# Solarduino_V0_4.net
KiCad netlist of a schematic drawn in EAGLE
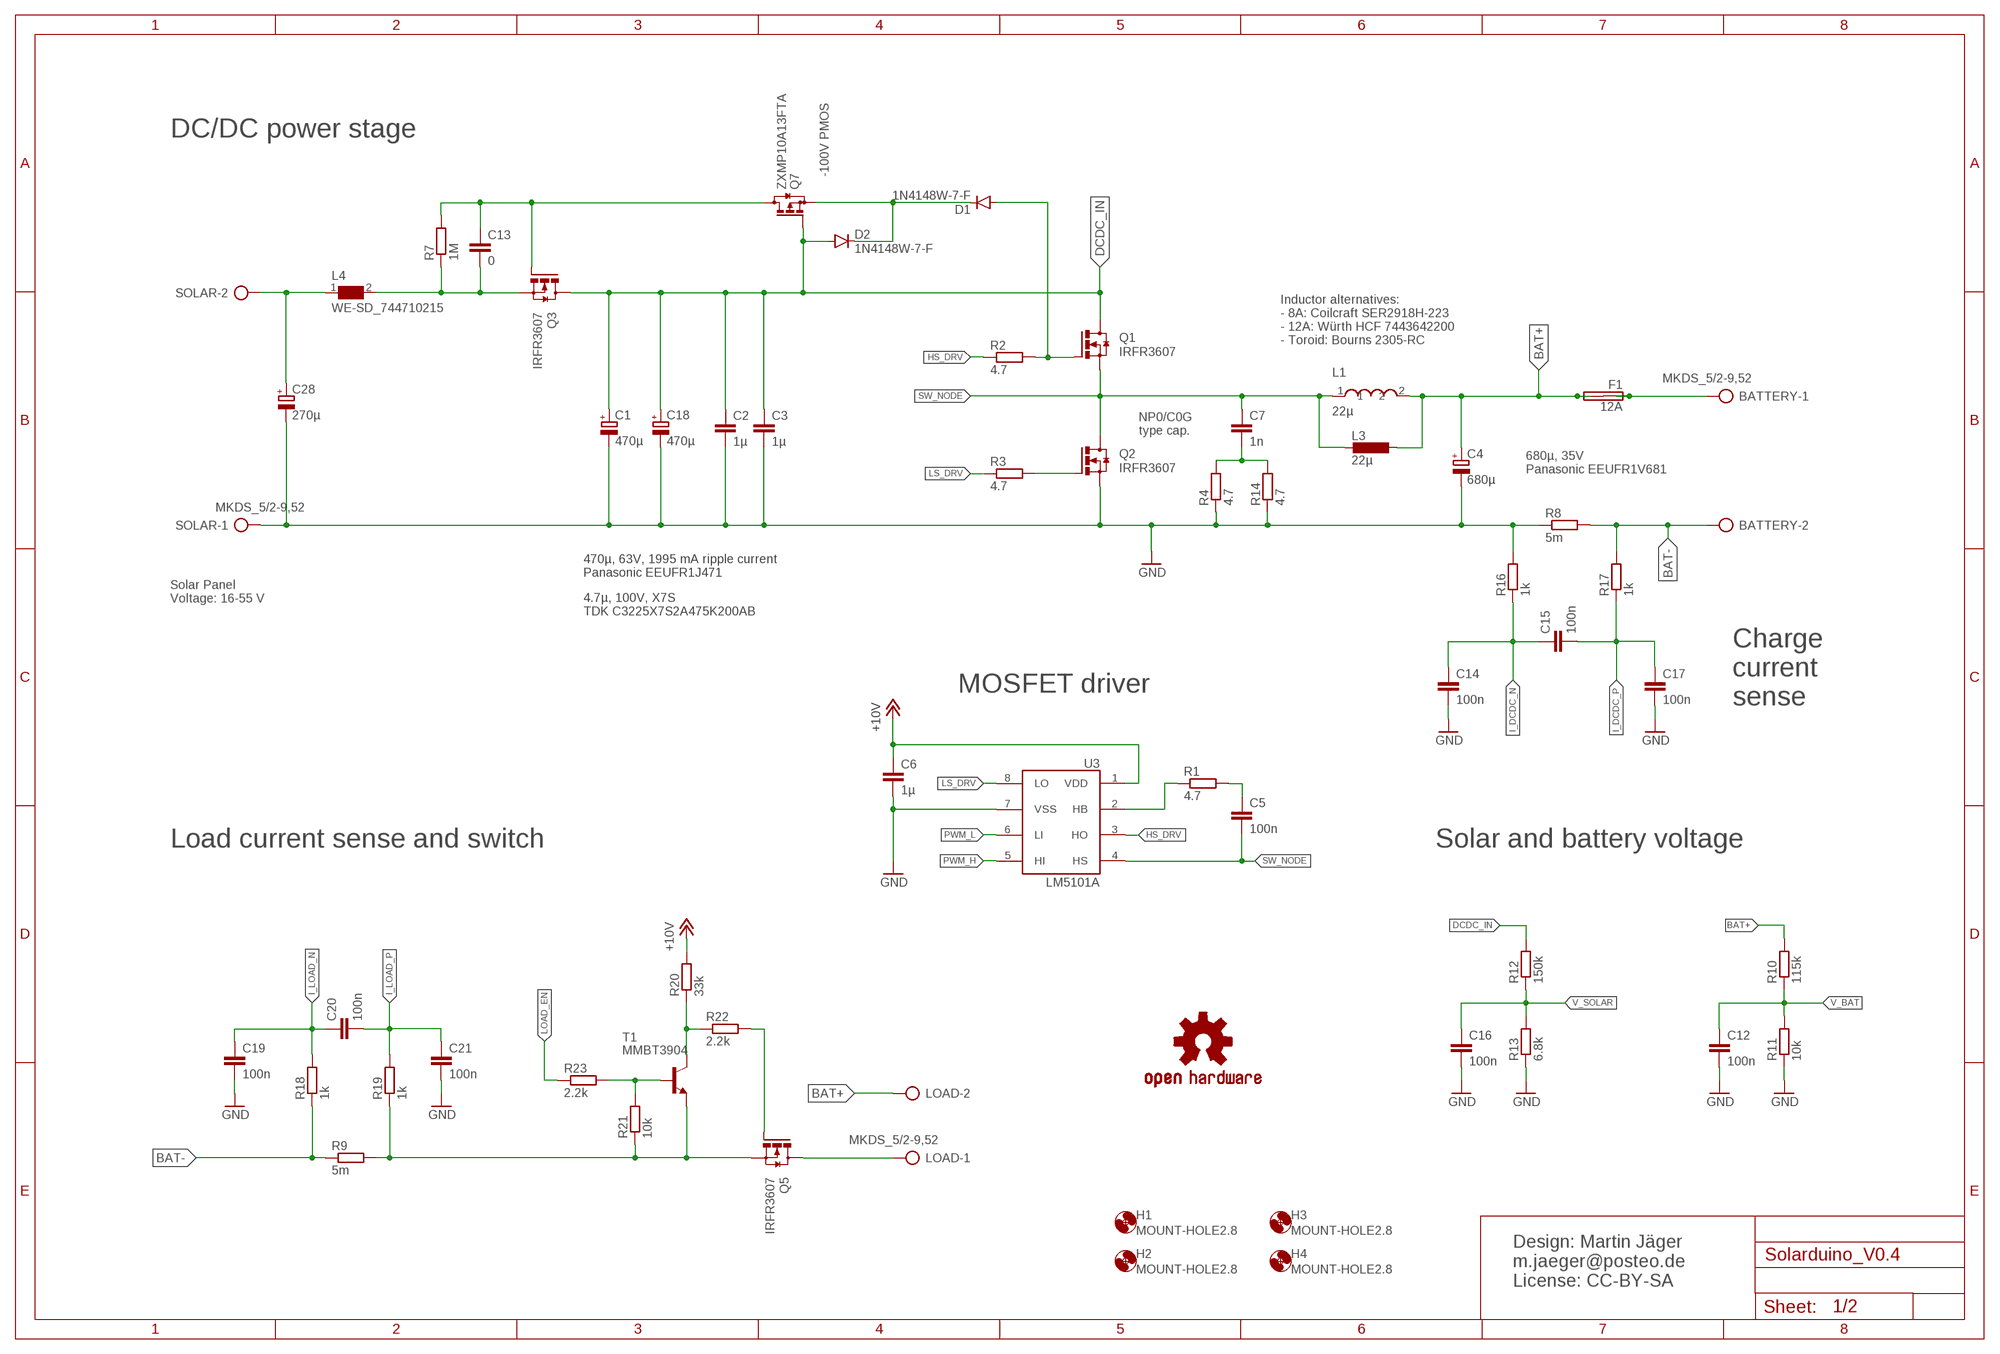
[diagram p0: schematic, sheet 1]
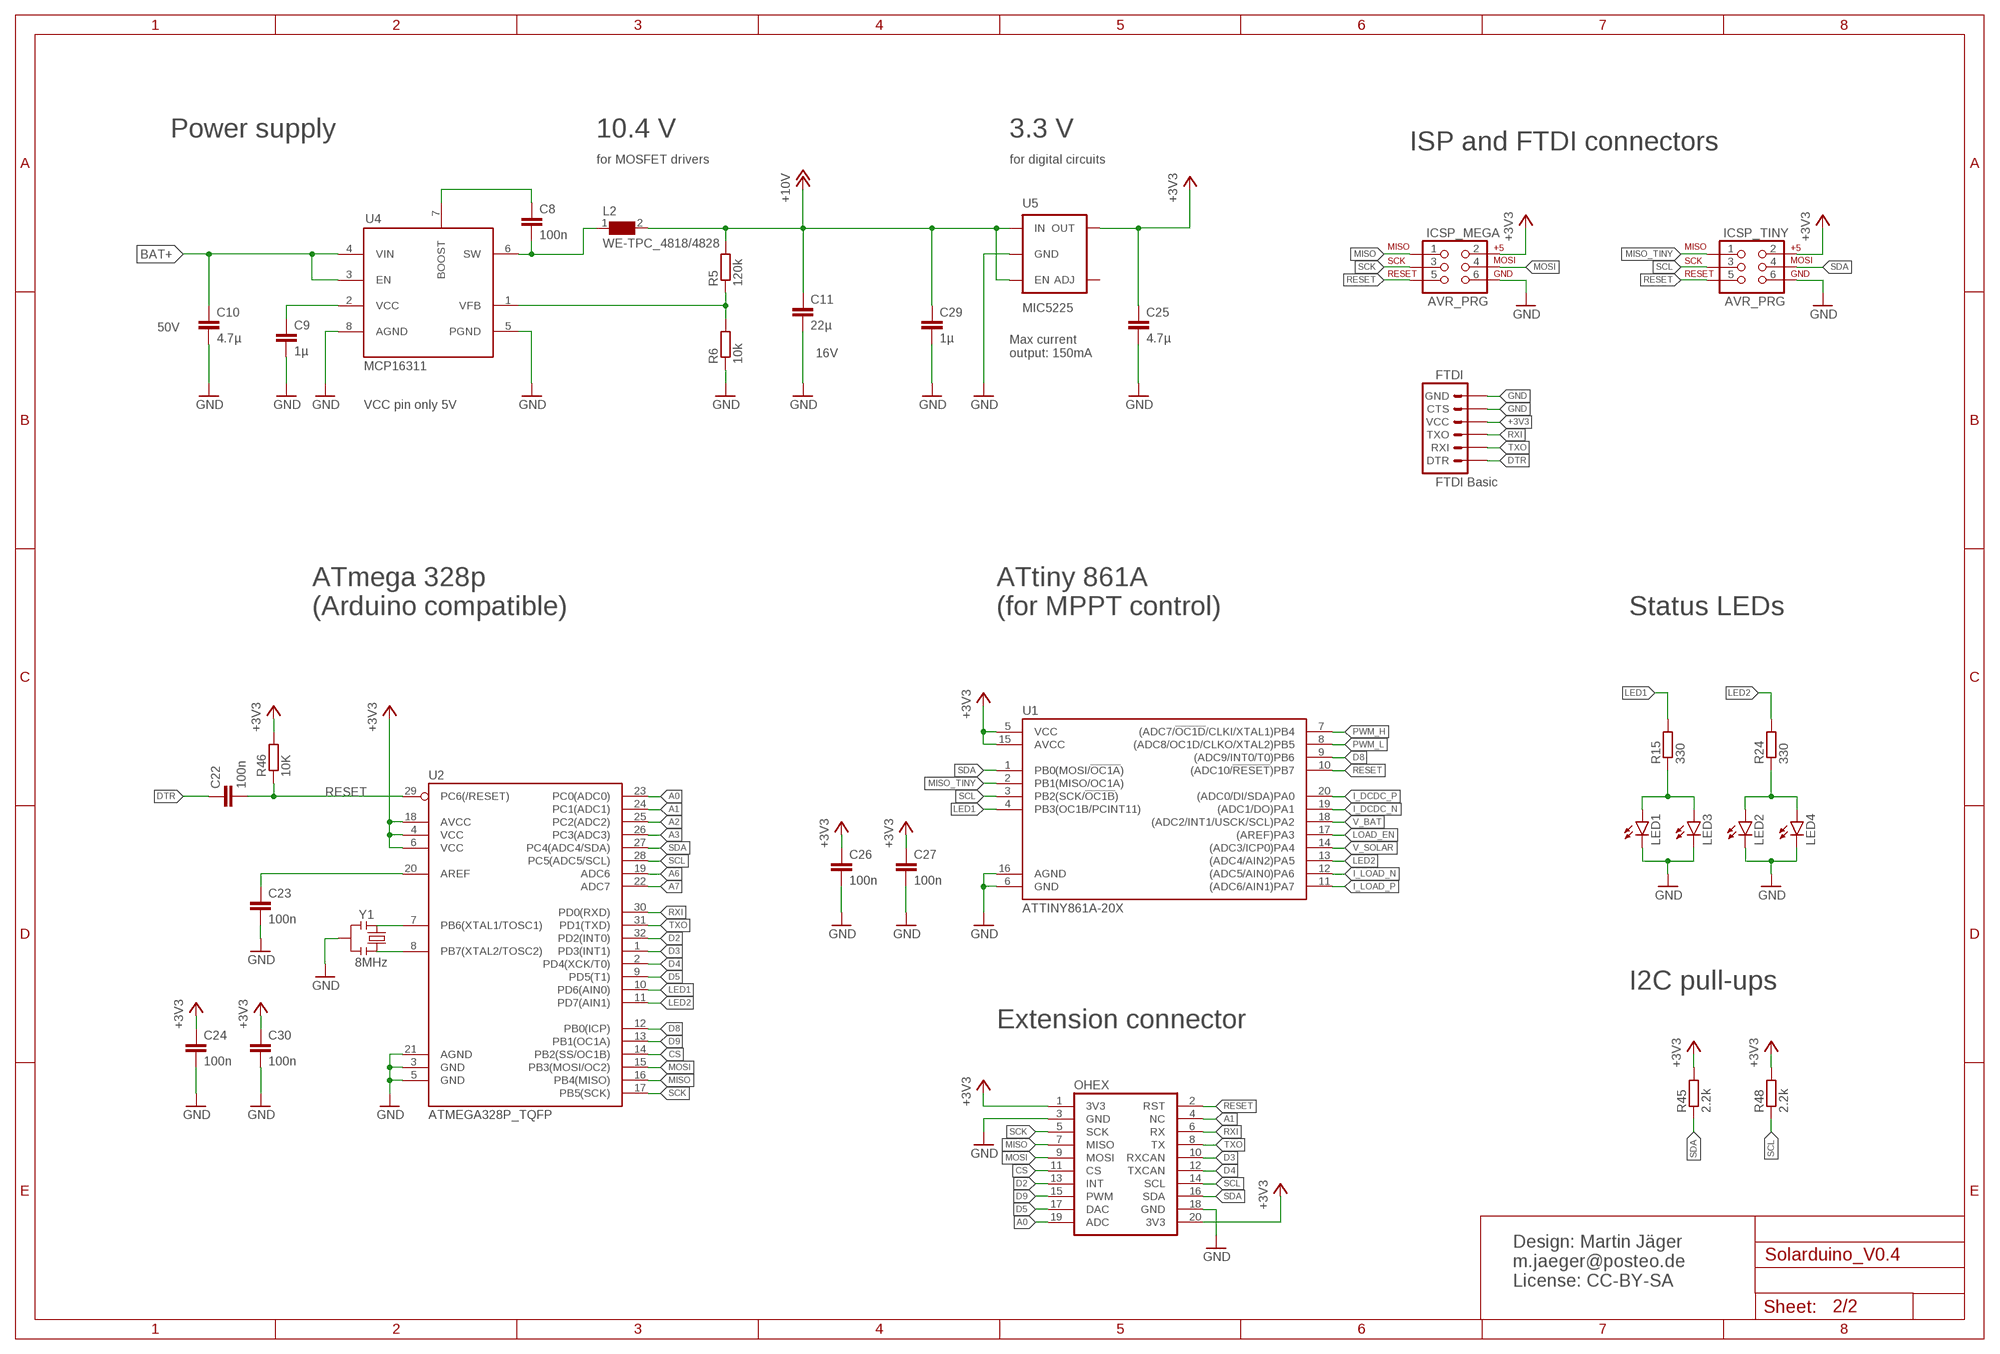
[diagram p1: schematic, sheet 2]

(export (version "E")
  (design (tool "Eeschema 10.0.6"))
  (components
    (comp (ref "BATTERY")
      (value "MKDS_5/2-9,52")
      (footprint "eagle-import:MKDS_5_2-952")
      (fields (field (name "OC_FARNELL") "unknown"))
      (libsource (lib "eagle-import") (part "MKDS_5/2-9,52"))
    )
    (comp (ref "C1")
      (value "470µ")
      (footprint "eagle-import:E5-13")
      (fields (field (name "MF") "PANASONIC ELECTRONIC COMPONENTS") (field (name "MPN") "EEUFR1J331B"))
      (libsource (lib "eagle-import") (part "CPOL-EUE5-13"))
    )
    (comp (ref "C2")
      (value "1µ")
      (footprint "eagle-import:C0805")
      (fields (field (name "MF") "TDK") (field (name "MPN") "C3225X7S2A475K200AB"))
      (libsource (lib "eagle-import") (part "C-EUC0805"))
    )
    (comp (ref "C3")
      (value "1µ")
      (footprint "eagle-import:C0805")
      (fields (field (name "MF") "TDK") (field (name "MPN") "C3225X7S2A475K200AB"))
      (libsource (lib "eagle-import") (part "C-EUC0805"))
    )
    (comp (ref "C4")
      (value "680µ")
      (footprint "eagle-import:E5-10,5")
      (fields (field (name "MF") "PANASONIC ELECTRONIC COMPONENTS") (field (name "MPN") "EEUFR1E821B"))
      (libsource (lib "eagle-import") (part "CPOL-EUE5-10.5"))
    )
    (comp (ref "C5")
      (value "100n")
      (footprint "eagle-import:C0603")
      (fields (field (name "MF") "AVX") (field (name "MPN") "08055C104KAT2A"))
      (libsource (lib "eagle-import") (part "C-EUC0603"))
    )
    (comp (ref "C6")
      (value "1µ")
      (footprint "eagle-import:C0603")
      (fields (field (name "MF") "AVX") (field (name "MPN") "08055C104KAT2A"))
      (libsource (lib "eagle-import") (part "C-EUC0603"))
    )
    (comp (ref "C7")
      (value "1n")
      (footprint "eagle-import:C0805")
      (fields (field (name "MF") "AVX") (field (name "MPN") "08055C104KAT2A"))
      (libsource (lib "eagle-import") (part "C-EUC0805"))
    )
    (comp (ref "C12")
      (value "100n")
      (footprint "eagle-import:C0603")
      (fields (field (name "MF") "AVX") (field (name "MPN") "08055C104KAT2A"))
      (libsource (lib "eagle-import") (part "C-EUC0603"))
    )
    (comp (ref "C13")
      (value "0")
      (footprint "eagle-import:C0603")
      (fields (field (name "MF") "AVX") (field (name "MPN") "08055C104KAT2A"))
      (libsource (lib "eagle-import") (part "C-EUC0603"))
    )
    (comp (ref "C14")
      (value "100n")
      (footprint "eagle-import:C0603")
      (fields (field (name "MF") "AVX") (field (name "MPN") "08055C104KAT2A"))
      (libsource (lib "eagle-import") (part "C-EUC0603"))
    )
    (comp (ref "C15")
      (value "100n")
      (footprint "eagle-import:C0603")
      (fields (field (name "MF") "AVX") (field (name "MPN") "08055C104KAT2A"))
      (libsource (lib "eagle-import") (part "C-EUC0603"))
    )
    (comp (ref "C16")
      (value "100n")
      (footprint "eagle-import:C0603")
      (fields (field (name "MF") "AVX") (field (name "MPN") "08055C104KAT2A"))
      (libsource (lib "eagle-import") (part "C-EUC0603"))
    )
    (comp (ref "C17")
      (value "100n")
      (footprint "eagle-import:C0603")
      (fields (field (name "MF") "AVX") (field (name "MPN") "08055C104KAT2A"))
      (libsource (lib "eagle-import") (part "C-EUC0603"))
    )
    (comp (ref "C18")
      (value "470µ")
      (footprint "eagle-import:E5-13")
      (fields (field (name "MF") "PANASONIC ELECTRONIC COMPONENTS") (field (name "MPN") "EEUFR1J331B"))
      (libsource (lib "eagle-import") (part "CPOL-EUE5-13"))
    )
    (comp (ref "C19")
      (value "100n")
      (footprint "eagle-import:C0603")
      (fields (field (name "MF") "AVX") (field (name "MPN") "08055C104KAT2A"))
      (libsource (lib "eagle-import") (part "C-EUC0603"))
    )
    (comp (ref "C20")
      (value "100n")
      (footprint "eagle-import:C0603")
      (fields (field (name "MF") "AVX") (field (name "MPN") "08055C104KAT2A"))
      (libsource (lib "eagle-import") (part "C-EUC0603"))
    )
    (comp (ref "C21")
      (value "100n")
      (footprint "eagle-import:C0603")
      (fields (field (name "MF") "AVX") (field (name "MPN") "08055C104KAT2A"))
      (libsource (lib "eagle-import") (part "C-EUC0603"))
    )
    (comp (ref "C28")
      (value "270µ")
      (footprint "eagle-import:E5-10,5")
      (fields (field (name "MF") "PANASONIC ELECTRONIC COMPONENTS") (field (name "MPN") "EEUFR1E821B"))
      (libsource (lib "eagle-import") (part "CPOL-EUE5-10.5"))
    )
    (comp (ref "D1")
      (value "1N4148W-7-F")
      (footprint "eagle-import:SOD-123")
      (libsource (lib "eagle-import") (part "DIODESOD123"))
    )
    (comp (ref "D2")
      (value "1N4148W-7-F")
      (footprint "eagle-import:SOD-123")
      (libsource (lib "eagle-import") (part "DIODESOD123"))
    )
    (comp (ref "F1")
      (value "12A")
      (footprint "eagle-import:BLADE_FUSE_STD")
      (libsource (lib "eagle-import") (part "FUSE_BLADE_STD"))
    )
    (comp (ref "H1")
      (value "MOUNT-HOLE2.8")
      (footprint "eagle-import:2,8")
      (libsource (lib "eagle-import") (part "MOUNT-HOLE2.8"))
    )
    (comp (ref "H2")
      (value "MOUNT-HOLE2.8")
      (footprint "eagle-import:2,8")
      (libsource (lib "eagle-import") (part "MOUNT-HOLE2.8"))
    )
    (comp (ref "H3")
      (value "MOUNT-HOLE2.8")
      (footprint "eagle-import:2,8")
      (libsource (lib "eagle-import") (part "MOUNT-HOLE2.8"))
    )
    (comp (ref "H4")
      (value "MOUNT-HOLE2.8")
      (footprint "eagle-import:2,8")
      (libsource (lib "eagle-import") (part "MOUNT-HOLE2.8"))
    )
    (comp (ref "L1")
      (value "22µ")
      (footprint "eagle-import:WE-HCF_2818_7443643300")
      (fields (field (name "MF") "COILCRAFT") (field (name "MPN") "SER2918H-223KL"))
      (libsource (lib "eagle-import") (part "WE-HCF_2818_7443643300"))
    )
    (comp (ref "L3")
      (value "22µ")
      (footprint "eagle-import:L-BOURNS-2300-H")
      (libsource (lib "eagle-import") (part "L-BOURNS2300-H"))
    )
    (comp (ref "L4")
      (value "WE-SD_744710215")
      (footprint "eagle-import:WE-SD_744710215")
      (libsource (lib "eagle-import") (part "WE-SD_744710215"))
    )
    (comp (ref "LOAD")
      (value "MKDS_5/2-9,52")
      (footprint "eagle-import:MKDS_5_2-952")
      (fields (field (name "OC_FARNELL") "unknown"))
      (libsource (lib "eagle-import") (part "MKDS_5/2-9,52"))
    )
    (comp (ref "N1")
      (value "OSHW-LOGOM")
      (footprint "eagle-import:OSHW-LOGO-M")
      (libsource (lib "eagle-import") (part "OSHW-LOGOM"))
    )
    (comp (ref "Q1")
      (value "IRFR3607")
      (footprint "eagle-import:DPAK")
      (libsource (lib "eagle-import") (part "MOSFET_N_DPAK"))
    )
    (comp (ref "Q2")
      (value "IRFR3607")
      (footprint "eagle-import:DPAK")
      (libsource (lib "eagle-import") (part "MOSFET_N_DPAK"))
    )
    (comp (ref "Q3")
      (value "IRFR3607")
      (footprint "eagle-import:DPAK")
      (libsource (lib "eagle-import") (part "MOSFET_N_DPAK"))
    )
    (comp (ref "Q5")
      (value "IRFR3607")
      (footprint "eagle-import:DPAK")
      (libsource (lib "eagle-import") (part "MOSFET_N_DPAK"))
    )
    (comp (ref "Q7")
      (value "ZXMP10A13FTA")
      (footprint "eagle-import:SOT23")
      (fields (field (name "MF") "MULTICOMP") (field (name "MPN") "BSS84-7-F"))
      (libsource (lib "eagle-import") (part "BSS84"))
    )
    (comp (ref "R1")
      (value "4.7")
      (footprint "eagle-import:R0805")
      (fields (field (name "MF") "BOURNS") (field (name "MPN") "CR0805-FX-1001ELF"))
      (libsource (lib "eagle-import") (part "R-EU_R0805"))
    )
    (comp (ref "R2")
      (value "4.7")
      (footprint "eagle-import:R0805")
      (fields (field (name "MF") "BOURNS") (field (name "MPN") "CR0805-FX-1004ELF."))
      (libsource (lib "eagle-import") (part "R-EU_R0805"))
    )
    (comp (ref "R3")
      (value "4.7")
      (footprint "eagle-import:R0805")
      (fields (field (name "MF") "BOURNS") (field (name "MPN") "CR0805-FX-1004ELF."))
      (libsource (lib "eagle-import") (part "R-EU_R0805"))
    )
    (comp (ref "R4")
      (value "4.7")
      (footprint "eagle-import:R1206")
      (fields (field (name "MF") "BOURNS") (field (name "MPN") "CRM2010-JW-2R2ELF"))
      (libsource (lib "eagle-import") (part "R-EU_R1206"))
    )
    (comp (ref "R7")
      (value "1M")
      (footprint "eagle-import:R0603")
      (fields (field (name "MF") "BOURNS") (field (name "MPN") "CR0805-FX-1004ELF."))
      (libsource (lib "eagle-import") (part "R-EU_R0603"))
    )
    (comp (ref "R8")
      (value "5m")
      (footprint "eagle-import:R2512")
      (fields (field (name "MF") "BOURNS") (field (name "MPN") "CRF2512-FX-R005ELF"))
      (libsource (lib "eagle-import") (part "R-EU_R2512"))
    )
    (comp (ref "R9")
      (value "5m")
      (footprint "eagle-import:R2512")
      (fields (field (name "MF") "BOURNS") (field (name "MPN") "CRF2512-FX-R005ELF"))
      (libsource (lib "eagle-import") (part "R-EU_R2512"))
    )
    (comp (ref "R10")
      (value "115k")
      (footprint "eagle-import:R0603")
      (fields (field (name "MF") "PANASONIC ELECTRONIC COMPONENTS") (field (name "MPN") "ERA6AEB104V"))
      (libsource (lib "eagle-import") (part "R-EU_R0603"))
    )
    (comp (ref "R11")
      (value "10k")
      (footprint "eagle-import:R0603")
      (fields (field (name "MF") "PANASONIC ELECTRONIC COMPONENTS") (field (name "MPN") "ERA6AEB682V"))
      (libsource (lib "eagle-import") (part "R-EU_R0603"))
    )
    (comp (ref "R12")
      (value "150k")
      (footprint "eagle-import:R0603")
      (fields (field (name "MF") "PANASONIC ELECTRONIC COMPONENTS") (field (name "MPN") "ERA6AEB104V"))
      (libsource (lib "eagle-import") (part "R-EU_R0603"))
    )
    (comp (ref "R13")
      (value "6.8k")
      (footprint "eagle-import:R0603")
      (fields (field (name "MF") "PANASONIC ELECTRONIC COMPONENTS") (field (name "MPN") "ERA6AEB104V"))
      (libsource (lib "eagle-import") (part "R-EU_R0603"))
    )
    (comp (ref "R14")
      (value "4.7")
      (footprint "eagle-import:R1206")
      (fields (field (name "MF") "BOURNS") (field (name "MPN") "CRM2010-JW-2R2ELF"))
      (libsource (lib "eagle-import") (part "R-EU_R1206"))
    )
    (comp (ref "R16")
      (value "1k")
      (footprint "eagle-import:R0603")
      (fields (field (name "MF") "BOURNS") (field (name "MPN") "CRM2010-JW-2R2ELF"))
      (libsource (lib "eagle-import") (part "R-EU_R0603"))
    )
    (comp (ref "R17")
      (value "1k")
      (footprint "eagle-import:R0603")
      (fields (field (name "MF") "BOURNS") (field (name "MPN") "CRM2010-JW-2R2ELF"))
      (libsource (lib "eagle-import") (part "R-EU_R0603"))
    )
    (comp (ref "R18")
      (value "1k")
      (footprint "eagle-import:R0603")
      (fields (field (name "MF") "BOURNS") (field (name "MPN") "CRM2010-JW-2R2ELF"))
      (libsource (lib "eagle-import") (part "R-EU_R0603"))
    )
    (comp (ref "R19")
      (value "1k")
      (footprint "eagle-import:R0603")
      (fields (field (name "MF") "BOURNS") (field (name "MPN") "CRM2010-JW-2R2ELF"))
      (libsource (lib "eagle-import") (part "R-EU_R0603"))
    )
    (comp (ref "R20")
      (value "33k")
      (footprint "eagle-import:R0603")
      (fields (field (name "MF") "BOURNS") (field (name "MPN") "CRM2010-JW-2R2ELF"))
      (libsource (lib "eagle-import") (part "R-EU_R0603"))
    )
    (comp (ref "R21")
      (value "10k")
      (footprint "eagle-import:R0603")
      (fields (field (name "MF") "BOURNS") (field (name "MPN") "CRM2010-JW-2R2ELF"))
      (libsource (lib "eagle-import") (part "R-EU_R0603"))
    )
    (comp (ref "R22")
      (value "2.2k")
      (footprint "eagle-import:R0603")
      (fields (field (name "MF") "BOURNS") (field (name "MPN") "CR0805-FX-1004ELF."))
      (libsource (lib "eagle-import") (part "R-EU_R0603"))
    )
    (comp (ref "R23")
      (value "2.2k")
      (footprint "eagle-import:R0603")
      (fields (field (name "MF") "BOURNS") (field (name "MPN") "CR0805-FX-1004ELF."))
      (libsource (lib "eagle-import") (part "R-EU_R0603"))
    )
    (comp (ref "SOLAR")
      (value "MKDS_5/2-9,52")
      (footprint "eagle-import:MKDS_5_2-952")
      (fields (field (name "OC_FARNELL") "unknown"))
      (libsource (lib "eagle-import") (part "MKDS_5/2-9,52"))
    )
    (comp (ref "T1")
      (value "MMBT3904")
      (footprint "eagle-import:SOT23-BEC")
      (libsource (lib "eagle-import") (part "-NPN-SOT23-BECMMBT3904LT1"))
    )
    (comp (ref "U3")
      (value "LM5101A")
      (footprint "eagle-import:SOIC-8-N")
      (libsource (lib "eagle-import") (part "LM5101A"))
    )
    (comp (ref "C8")
      (value "100n")
      (footprint "eagle-import:C0603")
      (fields (field (name "MF") "AVX") (field (name "MPN") "08055C104KAT2A"))
      (libsource (lib "eagle-import") (part "C-EUC0603"))
    )
    (comp (ref "C9")
      (value "1µ")
      (footprint "eagle-import:C0603")
      (fields (field (name "MF") "AVX") (field (name "MPN") "08055C104KAT2A"))
      (libsource (lib "eagle-import") (part "C-EUC0603"))
    )
    (comp (ref "C10")
      (value "4.7µ")
      (footprint "eagle-import:C1210")
      (fields (field (name "MF") "AVX") (field (name "MPN") "08055C104KAT2A"))
      (libsource (lib "eagle-import") (part "C-EUC1210"))
    )
    (comp (ref "C11")
      (value "22µ")
      (footprint "eagle-import:C1210")
      (fields (field (name "MF") "AVX") (field (name "MPN") "08055C104KAT2A"))
      (libsource (lib "eagle-import") (part "C-EUC1210"))
    )
    (comp (ref "C22")
      (value "100n")
      (footprint "eagle-import:C0603")
      (fields (field (name "MF") "AVX") (field (name "MPN") "08055C104KAT2A"))
      (libsource (lib "eagle-import") (part "C-EUC0603"))
    )
    (comp (ref "C23")
      (value "100n")
      (footprint "eagle-import:C0603")
      (fields (field (name "MF") "AVX") (field (name "MPN") "08055C104KAT2A"))
      (libsource (lib "eagle-import") (part "C-EUC0603"))
    )
    (comp (ref "C24")
      (value "100n")
      (footprint "eagle-import:C0603")
      (fields (field (name "MF") "AVX") (field (name "MPN") "08055C104KAT2A"))
      (libsource (lib "eagle-import") (part "C-EUC0603"))
    )
    (comp (ref "C25")
      (value "4.7µ")
      (footprint "eagle-import:C0603")
      (fields (field (name "MF") "AVX") (field (name "MPN") "0805YC475KAT2A"))
      (libsource (lib "eagle-import") (part "C-EUC0603"))
    )
    (comp (ref "C26")
      (value "100n")
      (footprint "eagle-import:C0603")
      (fields (field (name "MF") "AVX") (field (name "MPN") "08055C104KAT2A"))
      (libsource (lib "eagle-import") (part "C-EUC0603"))
    )
    (comp (ref "C27")
      (value "100n")
      (footprint "eagle-import:C0603")
      (fields (field (name "MF") "AVX") (field (name "MPN") "08055C104KAT2A"))
      (libsource (lib "eagle-import") (part "C-EUC0603"))
    )
    (comp (ref "C29")
      (value "1µ")
      (footprint "eagle-import:C0603")
      (fields (field (name "MF") "AVX") (field (name "MPN") "08053C105KAT2A"))
      (libsource (lib "eagle-import") (part "C-EUC0603"))
    )
    (comp (ref "C30")
      (value "100n")
      (footprint "eagle-import:C0603")
      (fields (field (name "MF") "AVX") (field (name "MPN") "08055C104KAT2A"))
      (libsource (lib "eagle-import") (part "C-EUC0603"))
    )
    (comp (ref "FTDI")
      (value "FTDI Basic")
      (footprint "eagle-import:1X06")
      (fields (field (name "MF") "MULTICOMP") (field (name "MPN") "2212S-06SG-85"))
      (libsource (lib "eagle-import") (part "ARDUINO_SERIAL_PROGRAMPTH"))
    )
    (comp (ref "ICSP_MEGA")
      (value "AVR_PRG")
      (footprint "eagle-import:2X3")
      (libsource (lib "eagle-import") (part "AVR_SPI_PRG_6PTH"))
    )
    (comp (ref "ICSP_TINY")
      (value "AVR_PRG")
      (footprint "eagle-import:2X3")
      (libsource (lib "eagle-import") (part "AVR_SPI_PRG_6PTH"))
    )
    (comp (ref "L2")
      (value "WE-TPC_4818/4828")
      (footprint "eagle-import:WE-TPC_4818_4828")
      (libsource (lib "eagle-import") (part "WE-TPC_4818/4828"))
    )
    (comp (ref "LED1")
      (value "LED3MM")
      (footprint "eagle-import:LED3MM")
      (libsource (lib "eagle-import") (part "LED3MM"))
    )
    (comp (ref "LED2")
      (value "LED3MM")
      (footprint "eagle-import:LED3MM")
      (libsource (lib "eagle-import") (part "LED3MM"))
    )
    (comp (ref "LED3")
      (value "LED0603")
      (footprint "eagle-import:LED-0603")
      (libsource (lib "eagle-import") (part "LED0603"))
    )
    (comp (ref "LED4")
      (value "LED0603")
      (footprint "eagle-import:LED-0603")
      (libsource (lib "eagle-import") (part "LED0603"))
    )
    (comp (ref "OHEX")
      (value "OHEX")
      (footprint "eagle-import:OHEX_SMALL")
      (libsource (lib "eagle-import") (part "OHEX"))
    )
    (comp (ref "R5")
      (value "120k")
      (footprint "eagle-import:R0603")
      (fields (field (name "MF") "BOURNS") (field (name "MPN") "CR0805-FX-1001ELF"))
      (libsource (lib "eagle-import") (part "R-EU_R0603"))
    )
    (comp (ref "R6")
      (value "10k")
      (footprint "eagle-import:R0603")
      (fields (field (name "MF") "BOURNS") (field (name "MPN") "CR0805-FX-1001ELF"))
      (libsource (lib "eagle-import") (part "R-EU_R0603"))
    )
    (comp (ref "R15")
      (value "330")
      (footprint "eagle-import:R0603")
      (fields (field (name "MF") "MULTICOMP") (field (name "MPN") "MCMR06X1001FTL"))
      (libsource (lib "eagle-import") (part "R-EU_R0603"))
    )
    (comp (ref "R24")
      (value "330")
      (footprint "eagle-import:R0603")
      (fields (field (name "MF") "MULTICOMP") (field (name "MPN") "MCMR06X1001FTL"))
      (libsource (lib "eagle-import") (part "R-EU_R0603"))
    )
    (comp (ref "R45")
      (value "2.2k")
      (footprint "eagle-import:R0603")
      (fields (field (name "MF") "BOURNS") (field (name "MPN") "CR0805-FX-1001ELF"))
      (libsource (lib "eagle-import") (part "R-EU_R0603"))
    )
    (comp (ref "R46")
      (value "10K")
      (footprint "eagle-import:R0603")
      (fields (field (name "MF") "BOURNS") (field (name "MPN") "CR0805-FX-1002ELF"))
      (libsource (lib "eagle-import") (part "R-EU_R0603"))
    )
    (comp (ref "R48")
      (value "2.2k")
      (footprint "eagle-import:R0603")
      (fields (field (name "MF") "BOURNS") (field (name "MPN") "CR0805-FX-1001ELF"))
      (libsource (lib "eagle-import") (part "R-EU_R0603"))
    )
    (comp (ref "U1")
      (value "ATTINY861A-20X")
      (footprint "eagle-import:TSSOP20")
      (libsource (lib "eagle-import") (part "ATTINY861A-20X"))
    )
    (comp (ref "U2")
      (value "ATMEGA328P_TQFP")
      (footprint "eagle-import:TQFP32-08")
      (libsource (lib "eagle-import") (part "ATMEGA328P-TQFP"))
    )
    (comp (ref "U4")
      (value "MCP16311")
      (footprint "eagle-import:MSOP8")
      (libsource (lib "eagle-import") (part "MCP16311"))
    )
    (comp (ref "U5")
      (value "MIC5225")
      (footprint "eagle-import:SOT23-5")
      (fields (field (name "MF") "MICROCHIP") (field (name "MPN") "MIC5225-3.3YM5-TR"))
      (libsource (lib "eagle-import") (part "V_REG_MIC5235"))
    )
    (comp (ref "Y1")
      (value "8MHz")
      (footprint "eagle-import:RESONATOR-SMD")
      (fields (field (name "MF") "MURATA") (field (name "MPN") "CSTCE8M00G55-R0"))
      (libsource (lib "eagle-import") (part "RESONATORSMD"))
    )
  )
  (nets
    (net (code "1") (name "+3V3") (class "Default")
      (node (ref "C24") (pin "1") (pinfunction "1_1") (pintype "passive"))
      (node (ref "C25") (pin "1") (pinfunction "1_1") (pintype "passive"))
      (node (ref "C26") (pin "1") (pinfunction "1_1") (pintype "passive"))
      (node (ref "C27") (pin "1") (pinfunction "1_1") (pintype "passive"))
      (node (ref "C30") (pin "1") (pinfunction "1_1") (pintype "passive"))
      (node (ref "FTDI") (pin "4") (pinfunction "VCC_4") (pintype "passive"))
      (node (ref "ICSP_MEGA") (pin "2") (pinfunction "2_2") (pintype "passive"))
      (node (ref "ICSP_TINY") (pin "2") (pinfunction "2_2") (pintype "passive"))
      (node (ref "OHEX") (pin "1") (pinfunction "3V3_1") (pintype "power_in"))
      (node (ref "OHEX") (pin "20") (pinfunction "3V3_20") (pintype "power_in"))
      (node (ref "R45") (pin "2") (pinfunction "2_2") (pintype "passive"))
      (node (ref "R46") (pin "2") (pinfunction "2_2") (pintype "passive"))
      (node (ref "R48") (pin "2") (pinfunction "2_2") (pintype "passive"))
      (node (ref "U1") (pin "15") (pinfunction "AVCC_15") (pintype "bidirectional"))
      (node (ref "U1") (pin "5") (pinfunction "VCC_5") (pintype "power_in"))
      (node (ref "U2") (pin "18") (pinfunction "AVCC_18") (pintype "bidirectional"))
      (node (ref "U2") (pin "4") (pinfunction "VCC_4") (pintype "bidirectional"))
      (node (ref "U2") (pin "6") (pinfunction "VCC_6") (pintype "bidirectional"))
      (node (ref "U5") (pin "5") (pinfunction "OUT_5") (pintype "passive"))
    )
    (net (code "2") (name "+10V") (class "Default")
      (node (ref "C11") (pin "1") (pinfunction "1_1") (pintype "passive"))
      (node (ref "C29") (pin "1") (pinfunction "1_1") (pintype "passive"))
      (node (ref "C6") (pin "1") (pinfunction "1_1") (pintype "passive"))
      (node (ref "L2") (pin "2") (pinfunction "2_2") (pintype "passive"))
      (node (ref "R20") (pin "2") (pinfunction "2_2") (pintype "passive"))
      (node (ref "R5") (pin "2") (pinfunction "2_2") (pintype "passive"))
      (node (ref "U3") (pin "1") (pinfunction "VDD_1") (pintype "power_in"))
      (node (ref "U5") (pin "1") (pinfunction "IN_1") (pintype "input"))
      (node (ref "U5") (pin "3") (pinfunction "EN_3") (pintype "input"))
    )
    (net (code "3") (name "A0") (class "Default")
      (node (ref "OHEX") (pin "19") (pinfunction "ADC_19") (pintype "bidirectional"))
      (node (ref "U2") (pin "23") (pinfunction "PC0(ADC0)_23") (pintype "bidirectional"))
    )
    (net (code "4") (name "A1") (class "Default")
      (node (ref "OHEX") (pin "4") (pinfunction "NC_4") (pintype "bidirectional"))
      (node (ref "U2") (pin "24") (pinfunction "PC1(ADC1)_24") (pintype "bidirectional"))
    )
    (net (code "5") (name "A2") (class "Default")
      (node (ref "U2") (pin "25") (pinfunction "PC2(ADC2)_25") (pintype "bidirectional"))
    )
    (net (code "6") (name "A3") (class "Default")
      (node (ref "U2") (pin "26") (pinfunction "PC3(ADC3)_26") (pintype "bidirectional"))
    )
    (net (code "7") (name "A6") (class "Default")
      (node (ref "U2") (pin "19") (pinfunction "ADC6_19") (pintype "bidirectional"))
    )
    (net (code "8") (name "A7") (class "Default")
      (node (ref "U2") (pin "22") (pinfunction "ADC7_22") (pintype "bidirectional"))
    )
    (net (code "9") (name "BAT+") (class "Default")
      (node (ref "C10") (pin "1") (pinfunction "1_1") (pintype "passive"))
      (node (ref "C4") (pin "+") (pinfunction "+_+") (pintype "passive"))
      (node (ref "F1") (pin "P$3") (pinfunction "2A_P$3") (pintype "passive"))
      (node (ref "F1") (pin "P$4") (pinfunction "2B_P$4") (pintype "passive"))
      (node (ref "L1") (pin "2") (pinfunction "2_2") (pintype "bidirectional"))
      (node (ref "L3") (pin "P$1") (pinfunction "1_P$1") (pintype "passive"))
      (node (ref "LOAD") (pin "2") (pinfunction "KL_2") (pintype "passive"))
      (node (ref "R10") (pin "2") (pinfunction "2_2") (pintype "passive"))
      (node (ref "U4") (pin "3") (pinfunction "EN_3") (pintype "bidirectional"))
      (node (ref "U4") (pin "4") (pinfunction "VIN_4") (pintype "bidirectional"))
    )
    (net (code "10") (name "BAT-") (class "Default")
      (node (ref "BATTERY") (pin "2") (pinfunction "KL_2") (pintype "passive"))
      (node (ref "R17") (pin "2") (pinfunction "2_2") (pintype "passive"))
      (node (ref "R18") (pin "1") (pinfunction "1_1") (pintype "passive"))
      (node (ref "R8") (pin "2") (pinfunction "2_2") (pintype "passive"))
      (node (ref "R9") (pin "1") (pinfunction "1_1") (pintype "passive"))
    )
    (net (code "11") (name "CS") (class "Default")
      (node (ref "OHEX") (pin "11") (pinfunction "CS_11") (pintype "bidirectional"))
      (node (ref "U2") (pin "14") (pinfunction "PB2(SS/OC1B)_14") (pintype "bidirectional"))
    )
    (net (code "12") (name "D2") (class "Default")
      (node (ref "OHEX") (pin "13") (pinfunction "INT_13") (pintype "bidirectional"))
      (node (ref "U2") (pin "32") (pinfunction "PD2(INT0)_32") (pintype "bidirectional"))
    )
    (net (code "13") (name "D3") (class "Default")
      (node (ref "OHEX") (pin "10") (pinfunction "RXCAN_10") (pintype "bidirectional"))
      (node (ref "U2") (pin "1") (pinfunction "PD3(INT1)_1") (pintype "bidirectional"))
    )
    (net (code "14") (name "D4") (class "Default")
      (node (ref "OHEX") (pin "12") (pinfunction "TXCAN_12") (pintype "bidirectional"))
      (node (ref "U2") (pin "2") (pinfunction "PD4(XCK/T0)_2") (pintype "bidirectional"))
    )
    (net (code "15") (name "D5") (class "Default")
      (node (ref "OHEX") (pin "17") (pinfunction "DAC_17") (pintype "bidirectional"))
      (node (ref "U2") (pin "9") (pinfunction "PD5(T1)_9") (pintype "bidirectional"))
    )
    (net (code "16") (name "D8") (class "Default")
      (node (ref "U1") (pin "9") (pinfunction "(ADC9/INT0/T0)PB6_9") (pintype "bidirectional"))
      (node (ref "U2") (pin "12") (pinfunction "PB0(ICP)_12") (pintype "bidirectional"))
    )
    (net (code "17") (name "D9") (class "Default")
      (node (ref "OHEX") (pin "15") (pinfunction "PWM_15") (pintype "bidirectional"))
      (node (ref "U2") (pin "13") (pinfunction "PB1(OC1A)_13") (pintype "bidirectional"))
    )
    (net (code "18") (name "DCDC_IN") (class "Default")
      (node (ref "C1") (pin "+") (pinfunction "+_+") (pintype "passive"))
      (node (ref "C18") (pin "+") (pinfunction "+_+") (pintype "passive"))
      (node (ref "C2") (pin "1") (pinfunction "1_1") (pintype "passive"))
      (node (ref "C3") (pin "1") (pinfunction "1_1") (pintype "passive"))
      (node (ref "D2") (pin "A") (pinfunction "A_A") (pintype "passive"))
      (node (ref "Q1") (pin "4") (pinfunction "D_4") (pintype "passive"))
      (node (ref "Q3") (pin "4") (pinfunction "D_4") (pintype "passive"))
      (node (ref "Q7") (pin "1") (pinfunction "G_1") (pintype "passive"))
      (node (ref "R12") (pin "2") (pinfunction "2_2") (pintype "passive"))
    )
    (net (code "19") (name "DTR") (class "Default")
      (node (ref "C22") (pin "1") (pinfunction "1_1") (pintype "passive"))
      (node (ref "FTDI") (pin "1") (pinfunction "DTR_1") (pintype "passive"))
    )
    (net (code "20") (name "GND") (class "Default")
      (node (ref "C1") (pin "-") (pinfunction "-_-") (pintype "passive"))
      (node (ref "C10") (pin "2") (pinfunction "2_2") (pintype "passive"))
      (node (ref "C11") (pin "2") (pinfunction "2_2") (pintype "passive"))
      (node (ref "C12") (pin "2") (pinfunction "2_2") (pintype "passive"))
      (node (ref "C14") (pin "2") (pinfunction "2_2") (pintype "passive"))
      (node (ref "C16") (pin "2") (pinfunction "2_2") (pintype "passive"))
      (node (ref "C17") (pin "2") (pinfunction "2_2") (pintype "passive"))
      (node (ref "C18") (pin "-") (pinfunction "-_-") (pintype "passive"))
      (node (ref "C19") (pin "2") (pinfunction "2_2") (pintype "passive"))
      (node (ref "C2") (pin "2") (pinfunction "2_2") (pintype "passive"))
      (node (ref "C21") (pin "2") (pinfunction "2_2") (pintype "passive"))
      (node (ref "C23") (pin "2") (pinfunction "2_2") (pintype "passive"))
      (node (ref "C24") (pin "2") (pinfunction "2_2") (pintype "passive"))
      (node (ref "C25") (pin "2") (pinfunction "2_2") (pintype "passive"))
      (node (ref "C26") (pin "2") (pinfunction "2_2") (pintype "passive"))
      (node (ref "C27") (pin "2") (pinfunction "2_2") (pintype "passive"))
      (node (ref "C28") (pin "-") (pinfunction "-_-") (pintype "passive"))
      (node (ref "C29") (pin "2") (pinfunction "2_2") (pintype "passive"))
      (node (ref "C3") (pin "2") (pinfunction "2_2") (pintype "passive"))
      (node (ref "C30") (pin "2") (pinfunction "2_2") (pintype "passive"))
      (node (ref "C4") (pin "-") (pinfunction "-_-") (pintype "passive"))
      (node (ref "C6") (pin "2") (pinfunction "2_2") (pintype "passive"))
      (node (ref "C9") (pin "2") (pinfunction "2_2") (pintype "passive"))
      (node (ref "FTDI") (pin "5") (pinfunction "CTS_5") (pintype "passive"))
      (node (ref "FTDI") (pin "6") (pinfunction "GND_6") (pintype "passive"))
      (node (ref "ICSP_MEGA") (pin "6") (pinfunction "6_6") (pintype "passive"))
      (node (ref "ICSP_TINY") (pin "6") (pinfunction "6_6") (pintype "passive"))
      (node (ref "LED1") (pin "K") (pinfunction "C_K") (pintype "passive"))
      (node (ref "LED2") (pin "K") (pinfunction "C_K") (pintype "passive"))
      (node (ref "LED3") (pin "C") (pinfunction "C_C") (pintype "passive"))
      (node (ref "LED4") (pin "C") (pinfunction "C_C") (pintype "passive"))
      (node (ref "OHEX") (pin "18") (pinfunction "GND_18") (pintype "power_in"))
      (node (ref "OHEX") (pin "3") (pinfunction "GND_3") (pintype "power_in"))
      (node (ref "Q2") (pin "3") (pinfunction "S_3") (pintype "passive"))
      (node (ref "R11") (pin "1") (pinfunction "1_1") (pintype "passive"))
      (node (ref "R13") (pin "1") (pinfunction "1_1") (pintype "passive"))
      (node (ref "R14") (pin "1") (pinfunction "1_1") (pintype "passive"))
      (node (ref "R16") (pin "2") (pinfunction "2_2") (pintype "passive"))
      (node (ref "R4") (pin "1") (pinfunction "1_1") (pintype "passive"))
      (node (ref "R6") (pin "1") (pinfunction "1_1") (pintype "passive"))
      (node (ref "R8") (pin "1") (pinfunction "1_1") (pintype "passive"))
      (node (ref "SOLAR") (pin "1") (pinfunction "KL_1") (pintype "passive"))
      (node (ref "U1") (pin "16") (pinfunction "AGND_16") (pintype "bidirectional"))
      (node (ref "U1") (pin "6") (pinfunction "GND_6") (pintype "power_in"))
      (node (ref "U2") (pin "21") (pinfunction "AGND_21") (pintype "bidirectional"))
      (node (ref "U2") (pin "3") (pinfunction "GND_3") (pintype "bidirectional"))
      (node (ref "U2") (pin "5") (pinfunction "GND_5") (pintype "bidirectional"))
      (node (ref "U3") (pin "7") (pinfunction "VSS_7") (pintype "power_in"))
      (node (ref "U4") (pin "5") (pinfunction "PGND_5") (pintype "bidirectional"))
      (node (ref "U4") (pin "8") (pinfunction "AGND_8") (pintype "bidirectional"))
      (node (ref "U5") (pin "2") (pinfunction "GND_2") (pintype "input"))
      (node (ref "Y1") (pin "2") (pinfunction "2_2") (pintype "passive"))
    )
    (net (code "21") (name "HS_DRV") (class "Default")
      (node (ref "R2") (pin "1") (pinfunction "1_1") (pintype "passive"))
      (node (ref "U3") (pin "3") (pinfunction "HO_3") (pintype "output"))
    )
    (net (code "22") (name "I_DCDC_N") (class "Default")
      (node (ref "C14") (pin "1") (pinfunction "1_1") (pintype "passive"))
      (node (ref "C15") (pin "1") (pinfunction "1_1") (pintype "passive"))
      (node (ref "R16") (pin "1") (pinfunction "1_1") (pintype "passive"))
      (node (ref "U1") (pin "19") (pinfunction "(ADC1/DO)PA1_19") (pintype "bidirectional"))
    )
    (net (code "23") (name "I_DCDC_P") (class "Default")
      (node (ref "C15") (pin "2") (pinfunction "2_2") (pintype "passive"))
      (node (ref "C17") (pin "1") (pinfunction "1_1") (pintype "passive"))
      (node (ref "R17") (pin "1") (pinfunction "1_1") (pintype "passive"))
      (node (ref "U1") (pin "20") (pinfunction "(ADC0/DI/SDA)PA0_20") (pintype "bidirectional"))
    )
    (net (code "24") (name "I_LOAD_N") (class "Default")
      (node (ref "C19") (pin "1") (pinfunction "1_1") (pintype "passive"))
      (node (ref "C20") (pin "1") (pinfunction "1_1") (pintype "passive"))
      (node (ref "R18") (pin "2") (pinfunction "2_2") (pintype "passive"))
      (node (ref "U1") (pin "12") (pinfunction "(ADC5/AIN0)PA6_12") (pintype "bidirectional"))
    )
    (net (code "25") (name "I_LOAD_P") (class "Default")
      (node (ref "C20") (pin "2") (pinfunction "2_2") (pintype "passive"))
      (node (ref "C21") (pin "1") (pinfunction "1_1") (pintype "passive"))
      (node (ref "R19") (pin "2") (pinfunction "2_2") (pintype "passive"))
      (node (ref "U1") (pin "11") (pinfunction "(ADC6/AIN1)PA7_11") (pintype "bidirectional"))
    )
    (net (code "26") (name "LED1") (class "Default")
      (node (ref "R15") (pin "2") (pinfunction "2_2") (pintype "passive"))
      (node (ref "U1") (pin "4") (pinfunction "PB3(OC1B/PCINT11)_4") (pintype "bidirectional"))
      (node (ref "U2") (pin "10") (pinfunction "PD6(AIN0)_10") (pintype "bidirectional"))
    )
    (net (code "27") (name "LED2") (class "Default")
      (node (ref "R24") (pin "2") (pinfunction "2_2") (pintype "passive"))
      (node (ref "U1") (pin "13") (pinfunction "(ADC4/AIN2)PA5_13") (pintype "bidirectional"))
      (node (ref "U2") (pin "11") (pinfunction "PD7(AIN1)_11") (pintype "bidirectional"))
    )
    (net (code "28") (name "LOAD_EN") (class "Default")
      (node (ref "R23") (pin "1") (pinfunction "1_1") (pintype "passive"))
      (node (ref "U1") (pin "17") (pinfunction "(AREF)PA3_17") (pintype "bidirectional"))
    )
    (net (code "29") (name "LS_DRV") (class "Default")
      (node (ref "R3") (pin "1") (pinfunction "1_1") (pintype "passive"))
      (node (ref "U3") (pin "8") (pinfunction "LO_8") (pintype "output"))
    )
    (net (code "30") (name "MISO") (class "Default")
      (node (ref "ICSP_MEGA") (pin "1") (pinfunction "1_1") (pintype "passive"))
      (node (ref "OHEX") (pin "7") (pinfunction "MISO_7") (pintype "bidirectional"))
      (node (ref "U2") (pin "16") (pinfunction "PB4(MISO)_16") (pintype "bidirectional"))
    )
    (net (code "31") (name "MISO_TINY") (class "Default")
      (node (ref "ICSP_TINY") (pin "1") (pinfunction "1_1") (pintype "passive"))
      (node (ref "U1") (pin "2") (pinfunction "PB1(MISO/OC1A)_2") (pintype "bidirectional"))
    )
    (net (code "32") (name "MOSI") (class "Default")
      (node (ref "ICSP_MEGA") (pin "4") (pinfunction "4_4") (pintype "passive"))
      (node (ref "OHEX") (pin "9") (pinfunction "MOSI_9") (pintype "bidirectional"))
      (node (ref "U2") (pin "15") (pinfunction "PB3(MOSI/OC2)_15") (pintype "bidirectional"))
    )
    (net (code "33") (name "Net-(BATTERYA-KL)") (class "Default")
      (node (ref "BATTERY") (pin "1") (pinfunction "KL_1") (pintype "passive"))
      (node (ref "F1") (pin "P$1") (pinfunction "1A_P$1") (pintype "passive"))
      (node (ref "F1") (pin "P$2") (pinfunction "1B_P$2") (pintype "passive"))
    )
    (net (code "34") (name "Net-(C5-Pad1)") (class "Default")
      (node (ref "C5") (pin "1") (pinfunction "1_1") (pintype "passive"))
      (node (ref "R1") (pin "2") (pinfunction "2_2") (pintype "passive"))
    )
    (net (code "35") (name "Net-(C7-Pad2)") (class "Default")
      (node (ref "C7") (pin "2") (pinfunction "2_2") (pintype "passive"))
      (node (ref "R14") (pin "2") (pinfunction "2_2") (pintype "passive"))
      (node (ref "R4") (pin "2") (pinfunction "2_2") (pintype "passive"))
    )
    (net (code "36") (name "Net-(LED1-PadA)") (class "Default")
      (node (ref "LED1") (pin "A") (pinfunction "A_A") (pintype "passive"))
      (node (ref "LED3") (pin "A") (pinfunction "A_A") (pintype "passive"))
      (node (ref "R15") (pin "1") (pinfunction "1_1") (pintype "passive"))
    )
    (net (code "37") (name "Net-(LED2-PadA)") (class "Default")
      (node (ref "LED2") (pin "A") (pinfunction "A_A") (pintype "passive"))
      (node (ref "LED4") (pin "A") (pinfunction "A_A") (pintype "passive"))
      (node (ref "R24") (pin "1") (pinfunction "1_1") (pintype "passive"))
    )
    (net (code "38") (name "Net-(LOADA-KL)") (class "Default")
      (node (ref "LOAD") (pin "1") (pinfunction "KL_1") (pintype "passive"))
      (node (ref "Q5") (pin "4") (pinfunction "D_4") (pintype "passive"))
    )
    (net (code "39") (name "Net-(Q1-G)") (class "Default")
      (node (ref "D1") (pin "A") (pinfunction "A_A") (pintype "passive"))
      (node (ref "Q1") (pin "1") (pinfunction "G_1") (pintype "passive"))
      (node (ref "R2") (pin "2") (pinfunction "2_2") (pintype "passive"))
    )
    (net (code "40") (name "Net-(Q2-G)") (class "Default")
      (node (ref "Q2") (pin "1") (pinfunction "G_1") (pintype "passive"))
      (node (ref "R3") (pin "2") (pinfunction "2_2") (pintype "passive"))
    )
    (net (code "41") (name "Net-(Q3-G)") (class "Default")
      (node (ref "C13") (pin "1") (pinfunction "1_1") (pintype "passive"))
      (node (ref "Q3") (pin "1") (pinfunction "G_1") (pintype "passive"))
      (node (ref "Q7") (pin "3") (pinfunction "D_3") (pintype "passive"))
      (node (ref "R7") (pin "2") (pinfunction "2_2") (pintype "passive"))
    )
    (net (code "42") (name "Net-(Q3-S)") (class "Default")
      (node (ref "C13") (pin "2") (pinfunction "2_2") (pintype "passive"))
      (node (ref "L4") (pin "2") (pinfunction "2_2") (pintype "passive"))
      (node (ref "Q3") (pin "3") (pinfunction "S_3") (pintype "passive"))
      (node (ref "R7") (pin "1") (pinfunction "1_1") (pintype "passive"))
    )
    (net (code "43") (name "Net-(Q5-G)") (class "Default")
      (node (ref "Q5") (pin "1") (pinfunction "G_1") (pintype "passive"))
      (node (ref "R22") (pin "2") (pinfunction "2_2") (pintype "passive"))
    )
    (net (code "44") (name "Net-(Q5-S)") (class "Default")
      (node (ref "Q5") (pin "3") (pinfunction "S_3") (pintype "passive"))
      (node (ref "R19") (pin "1") (pinfunction "1_1") (pintype "passive"))
      (node (ref "R21") (pin "1") (pinfunction "1_1") (pintype "passive"))
      (node (ref "R9") (pin "2") (pinfunction "2_2") (pintype "passive"))
      (node (ref "T1") (pin "E") (pinfunction "E_E") (pintype "passive"))
    )
    (net (code "45") (name "Net-(Q7-S)") (class "Default")
      (node (ref "D1") (pin "C") (pinfunction "C_C") (pintype "passive"))
      (node (ref "D2") (pin "C") (pinfunction "C_C") (pintype "passive"))
      (node (ref "Q7") (pin "2") (pinfunction "S_2") (pintype "passive"))
    )
    (net (code "46") (name "Net-(R20-Pad1)") (class "Default")
      (node (ref "R20") (pin "1") (pinfunction "1_1") (pintype "passive"))
      (node (ref "R22") (pin "1") (pinfunction "1_1") (pintype "passive"))
      (node (ref "T1") (pin "C") (pinfunction "C_C") (pintype "passive"))
    )
    (net (code "47") (name "Net-(R21-Pad2)") (class "Default")
      (node (ref "R21") (pin "2") (pinfunction "2_2") (pintype "passive"))
      (node (ref "R23") (pin "2") (pinfunction "2_2") (pintype "passive"))
      (node (ref "T1") (pin "B") (pinfunction "B_B") (pintype "passive"))
    )
    (net (code "48") (name "Net-(SOLARB-KL)") (class "Default")
      (node (ref "C28") (pin "+") (pinfunction "+_+") (pintype "passive"))
      (node (ref "L4") (pin "1") (pinfunction "1_1") (pintype "passive"))
      (node (ref "SOLAR") (pin "2") (pinfunction "KL_2") (pintype "passive"))
    )
    (net (code "49") (name "Net-(U2-AREF)") (class "Default")
      (node (ref "C23") (pin "1") (pinfunction "1_1") (pintype "passive"))
      (node (ref "U2") (pin "20") (pinfunction "AREF_20") (pintype "bidirectional"))
    )
    (net (code "50") (name "Net-(U2-PB6(XTAL1{slash}TOSC1))") (class "Default")
      (node (ref "U2") (pin "7") (pinfunction "PB6(XTAL1/TOSC1)_7") (pintype "bidirectional"))
      (node (ref "Y1") (pin "1") (pinfunction "1_1") (pintype "passive"))
    )
    (net (code "51") (name "Net-(U2-PB7(XTAL2{slash}TOSC2))") (class "Default")
      (node (ref "U2") (pin "8") (pinfunction "PB7(XTAL2/TOSC2)_8") (pintype "bidirectional"))
      (node (ref "Y1") (pin "3") (pinfunction "3_3") (pintype "passive"))
    )
    (net (code "52") (name "Net-(U3-HB)") (class "Default")
      (node (ref "R1") (pin "1") (pinfunction "1_1") (pintype "passive"))
      (node (ref "U3") (pin "2") (pinfunction "HB_2") (pintype "input"))
    )
    (net (code "53") (name "Net-(U4-BOOST)") (class "Default")
      (node (ref "C8") (pin "1") (pinfunction "1_1") (pintype "passive"))
      (node (ref "U4") (pin "7") (pinfunction "BOOST_7") (pintype "bidirectional"))
    )
    (net (code "54") (name "Net-(U4-SW)") (class "Default")
      (node (ref "C8") (pin "2") (pinfunction "2_2") (pintype "passive"))
      (node (ref "L2") (pin "1") (pinfunction "1_1") (pintype "passive"))
      (node (ref "U4") (pin "6") (pinfunction "SW_6") (pintype "bidirectional"))
    )
    (net (code "55") (name "Net-(U4-VCC)") (class "Default")
      (node (ref "C9") (pin "1") (pinfunction "1_1") (pintype "passive"))
      (node (ref "U4") (pin "2") (pinfunction "VCC_2") (pintype "bidirectional"))
    )
    (net (code "56") (name "Net-(U4-VFB)") (class "Default")
      (node (ref "R5") (pin "1") (pinfunction "1_1") (pintype "passive"))
      (node (ref "R6") (pin "2") (pinfunction "2_2") (pintype "passive"))
      (node (ref "U4") (pin "1") (pinfunction "VFB_1") (pintype "bidirectional"))
    )
    (net (code "57") (name "PWM_H") (class "Default")
      (node (ref "U1") (pin "7") (pinfunction "(ADC7/~{OC1D}/CLKI/XTAL1)PB4_7") (pintype "bidirectional"))
      (node (ref "U3") (pin "5") (pinfunction "HI_5") (pintype "input"))
    )
    (net (code "58") (name "PWM_L") (class "Default")
      (node (ref "U1") (pin "8") (pinfunction "(ADC8/OC1D/CLKO/XTAL2)PB5_8") (pintype "bidirectional"))
      (node (ref "U3") (pin "6") (pinfunction "LI_6") (pintype "input"))
    )
    (net (code "59") (name "RESET") (class "Default")
      (node (ref "C22") (pin "2") (pinfunction "2_2") (pintype "passive"))
      (node (ref "ICSP_MEGA") (pin "5") (pinfunction "5_5") (pintype "passive"))
      (node (ref "ICSP_TINY") (pin "5") (pinfunction "5_5") (pintype "passive"))
      (node (ref "OHEX") (pin "2") (pinfunction "RST_2") (pintype "bidirectional"))
      (node (ref "R46") (pin "1") (pinfunction "1_1") (pintype "passive"))
      (node (ref "U1") (pin "10") (pinfunction "(ADC10/~{RESET})PB7_10") (pintype "bidirectional"))
      (node (ref "U2") (pin "29") (pinfunction "PC6(/RESET)_29") (pintype "bidirectional"))
    )
    (net (code "60") (name "RXI") (class "Default")
      (node (ref "FTDI") (pin "3") (pinfunction "TXO_3") (pintype "passive"))
      (node (ref "OHEX") (pin "6") (pinfunction "RX_6") (pintype "bidirectional"))
      (node (ref "U2") (pin "30") (pinfunction "PD0(RXD)_30") (pintype "bidirectional"))
    )
    (net (code "61") (name "SCK") (class "Default")
      (node (ref "ICSP_MEGA") (pin "3") (pinfunction "3_3") (pintype "passive"))
      (node (ref "OHEX") (pin "5") (pinfunction "SCK_5") (pintype "bidirectional"))
      (node (ref "U2") (pin "17") (pinfunction "PB5(SCK)_17") (pintype "bidirectional"))
    )
    (net (code "62") (name "SCL") (class "Default")
      (node (ref "ICSP_TINY") (pin "3") (pinfunction "3_3") (pintype "passive"))
      (node (ref "OHEX") (pin "14") (pinfunction "SCL_14") (pintype "bidirectional"))
      (node (ref "R48") (pin "1") (pinfunction "1_1") (pintype "passive"))
      (node (ref "U1") (pin "3") (pinfunction "PB2(SCK/~{OC1B})_3") (pintype "bidirectional"))
      (node (ref "U2") (pin "28") (pinfunction "PC5(ADC5/SCL)_28") (pintype "bidirectional"))
    )
    (net (code "63") (name "SDA") (class "Default")
      (node (ref "ICSP_TINY") (pin "4") (pinfunction "4_4") (pintype "passive"))
      (node (ref "OHEX") (pin "16") (pinfunction "SDA_16") (pintype "bidirectional"))
      (node (ref "R45") (pin "1") (pinfunction "1_1") (pintype "passive"))
      (node (ref "U1") (pin "1") (pinfunction "PB0(MOSI/~{OC1A})_1") (pintype "bidirectional"))
      (node (ref "U2") (pin "27") (pinfunction "PC4(ADC4/SDA)_27") (pintype "bidirectional"))
    )
    (net (code "64") (name "SW_NODE") (class "Default")
      (node (ref "C5") (pin "2") (pinfunction "2_2") (pintype "passive"))
      (node (ref "C7") (pin "1") (pinfunction "1_1") (pintype "passive"))
      (node (ref "L1") (pin "1") (pinfunction "1_1") (pintype "bidirectional"))
      (node (ref "L3") (pin "P$2") (pinfunction "2_P$2") (pintype "passive"))
      (node (ref "Q1") (pin "3") (pinfunction "S_3") (pintype "passive"))
      (node (ref "Q2") (pin "4") (pinfunction "D_4") (pintype "passive"))
      (node (ref "U3") (pin "4") (pinfunction "HS_4") (pintype "input"))
    )
    (net (code "65") (name "TXO") (class "Default")
      (node (ref "FTDI") (pin "2") (pinfunction "RXI_2") (pintype "passive"))
      (node (ref "OHEX") (pin "8") (pinfunction "TX_8") (pintype "bidirectional"))
      (node (ref "U2") (pin "31") (pinfunction "PD1(TXD)_31") (pintype "bidirectional"))
    )
    (net (code "66") (name "V_BAT") (class "Default")
      (node (ref "C12") (pin "1") (pinfunction "1_1") (pintype "passive"))
      (node (ref "R10") (pin "1") (pinfunction "1_1") (pintype "passive"))
      (node (ref "R11") (pin "2") (pinfunction "2_2") (pintype "passive"))
      (node (ref "U1") (pin "18") (pinfunction "(ADC2/INT1/USCK/SCL)PA2_18") (pintype "bidirectional"))
    )
    (net (code "67") (name "V_SOLAR") (class "Default")
      (node (ref "C16") (pin "1") (pinfunction "1_1") (pintype "passive"))
      (node (ref "R12") (pin "1") (pinfunction "1_1") (pintype "passive"))
      (node (ref "R13") (pin "2") (pinfunction "2_2") (pintype "passive"))
      (node (ref "U1") (pin "14") (pinfunction "(ADC3/ICP0)PA4_14") (pintype "bidirectional"))
    )
    (net (code "68") (name "unconnected-(U5-ADJ-Pad4)") (class "Default")
      (node (ref "U5") (pin "4") (pinfunction "ADJ_4") (pintype "input"))
    )
  )
)
